# High-Level_PCB_v3_0.net
KiCad netlist of a schematic drawn in EAGLE
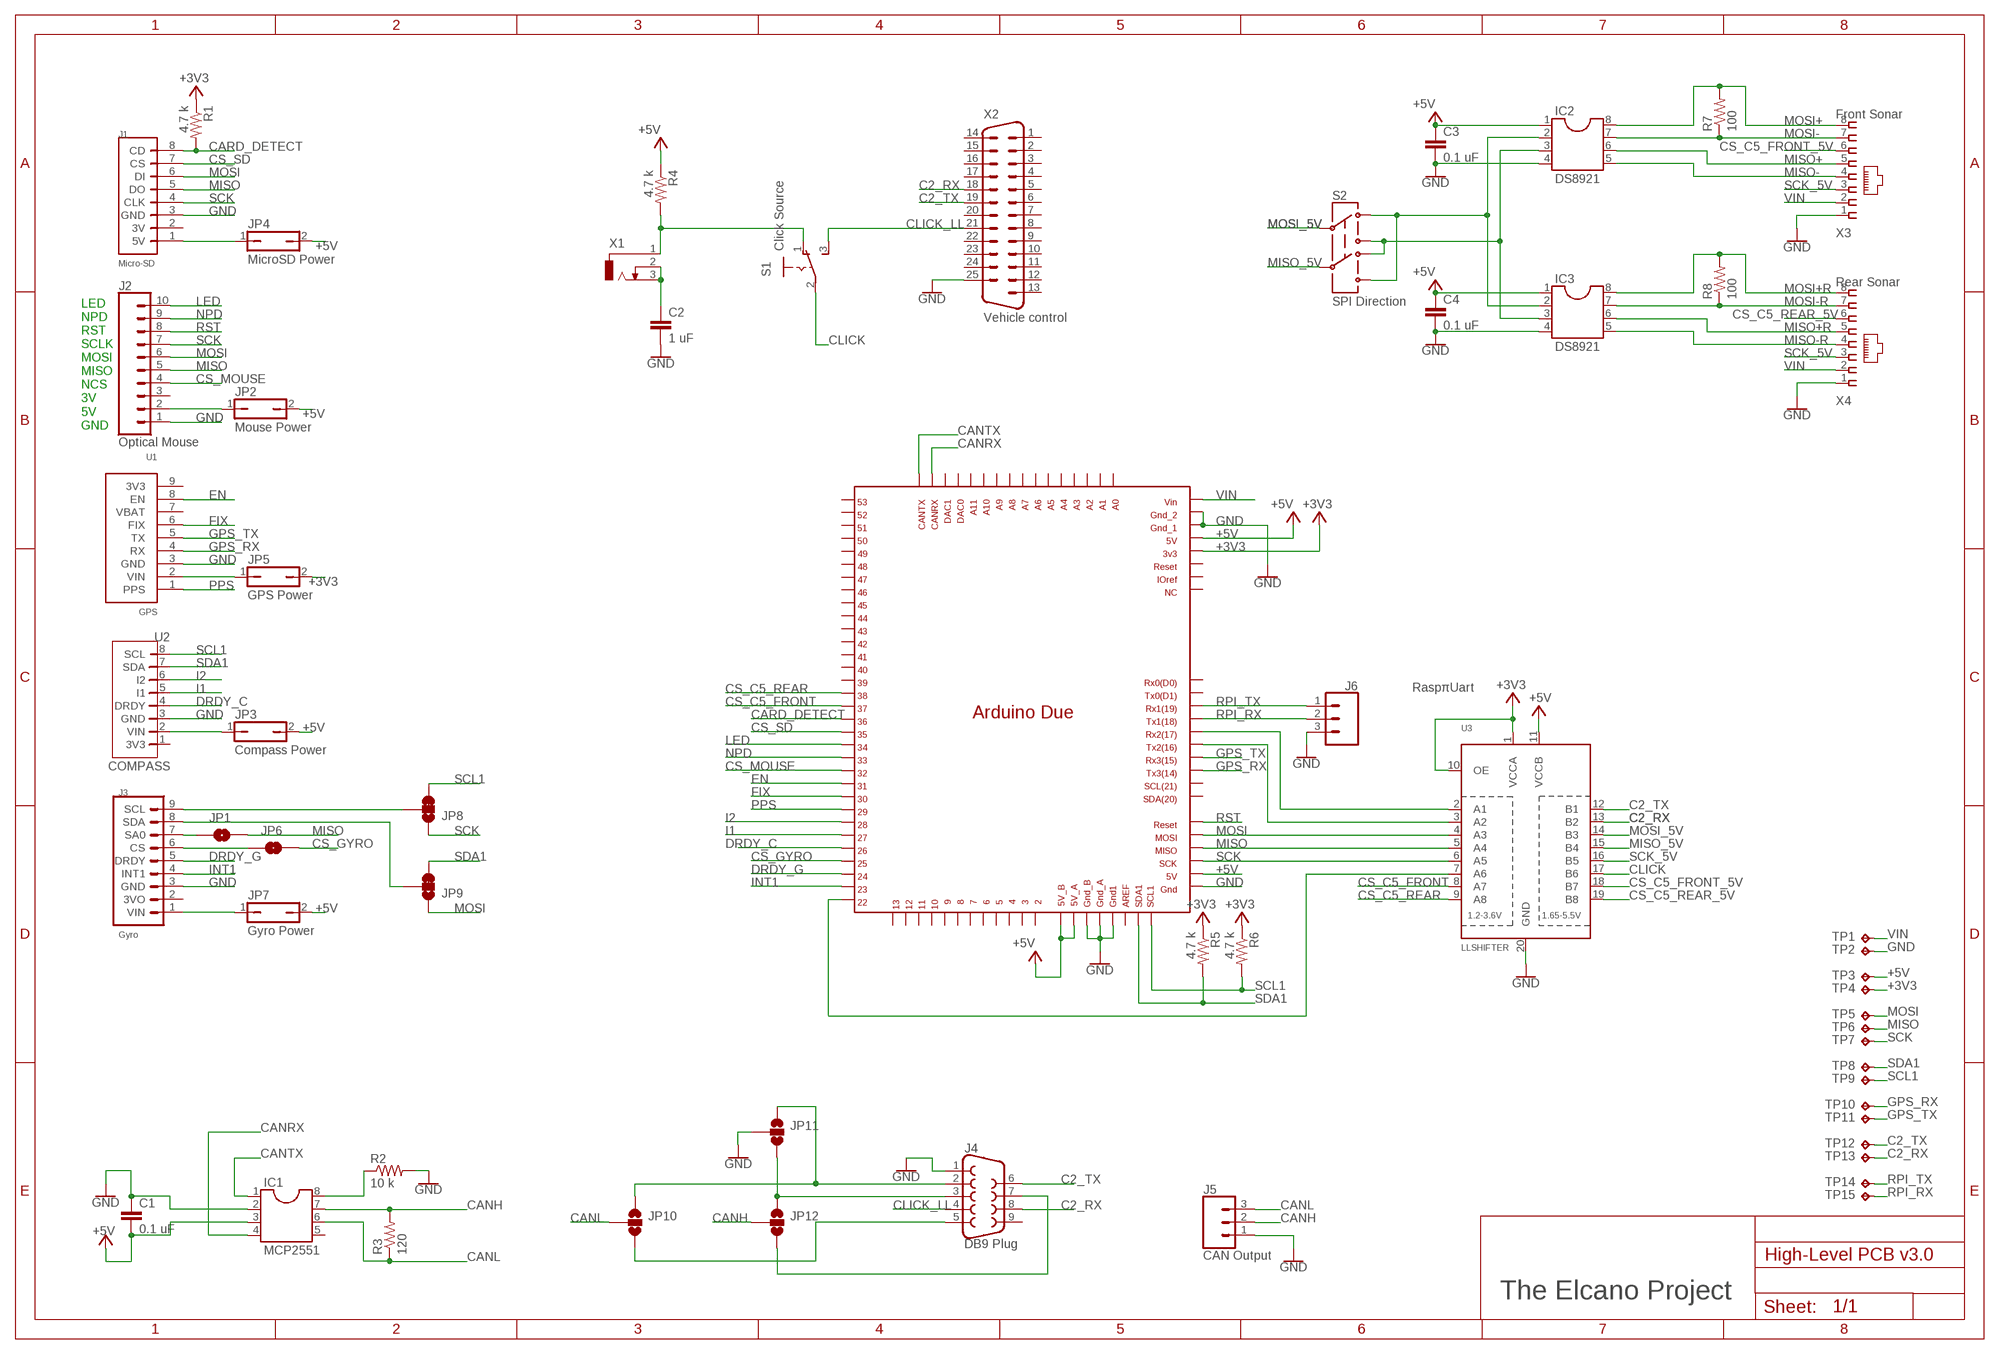
[diagram p0: schematic, sheet 1]

(export (version "E")
  (design (tool "Eeschema 10.0.6"))
  (components
    (comp (ref "C1")
      (value "0.1 uF")
      (footprint "eagle-import:C2.5-5")
      (libsource (lib "eagle-import") (part "C2.5/5"))
    )
    (comp (ref "C2")
      (value "1 uF")
      (footprint "eagle-import:C2.5-5")
      (libsource (lib "eagle-import") (part "C2.5/5"))
    )
    (comp (ref "C3")
      (value "0.1 uF")
      (footprint "eagle-import:C2.5-5")
      (libsource (lib "eagle-import") (part "C2.5/5"))
    )
    (comp (ref "C4")
      (value "0.1 uF")
      (footprint "eagle-import:C2.5-5")
      (libsource (lib "eagle-import") (part "C2.5/5"))
    )
    (comp (ref "IC1")
      (value "MCP2551")
      (footprint "eagle-import:DIL08")
      (libsource (lib "eagle-import") (part "DIL8"))
    )
    (comp (ref "IC2")
      (value "DS8921")
      (footprint "eagle-import:DIL08")
      (libsource (lib "eagle-import") (part "DIL8"))
    )
    (comp (ref "IC3")
      (value "DS8921")
      (footprint "eagle-import:DIL08")
      (libsource (lib "eagle-import") (part "DIL8"))
    )
    (comp (ref "J1")
      (value "Micro-SD")
      (footprint "eagle-import:ELSDCARD")
      (libsource (lib "eagle-import") (part "MINI_SD"))
    )
    (comp (ref "J2")
      (value "Optical Mouse")
      (footprint "eagle-import:1X10")
      (libsource (lib "eagle-import") (part "CONN_10{dblquote}"))
    )
    (comp (ref "J3")
      (value "Gyro")
      (footprint "eagle-import:ELGYRO")
      (libsource (lib "eagle-import") (part "ELGYRO_L3GD20H"))
    )
    (comp (ref "J4")
      (value "DB9 Plug")
      (footprint "eagle-import:DB9_MALE")
      (fields (field (name "SPICEPREFIX") "X"))
      (libsource (lib "eagle-import") (part "DB9MALE"))
    )
    (comp (ref "J5")
      (value "CAN Output")
      (footprint "eagle-import:SCREWTERMINAL-5MM-3")
      (libsource (lib "eagle-import") (part "CONN_03-SCREW-5MM"))
    )
    (comp (ref "J6")
      (value "RaspπUart")
      (footprint "eagle-import:1X03")
      (libsource (lib "eagle-import") (part "TXRX_2RSPPI"))
    )
    (comp (ref "JP1")
      (value "JUMPER-SMT_2_NO_SILK")
      (footprint "eagle-import:SMT-JUMPER_2_NO_SILK")
      (libsource (lib "eagle-import") (part "JUMPER-SMT_2_NO_SILK"))
    )
    (comp (ref "JP2")
      (value "Mouse Power")
      (footprint "eagle-import:JP1")
      (libsource (lib "eagle-import") (part "JP1Q"))
    )
    (comp (ref "JP3")
      (value "Compass Power")
      (footprint "eagle-import:JP1")
      (libsource (lib "eagle-import") (part "JP1Q"))
    )
    (comp (ref "JP4")
      (value "MicroSD Power")
      (footprint "eagle-import:JP1")
      (libsource (lib "eagle-import") (part "JP1Q"))
    )
    (comp (ref "JP5")
      (value "GPS Power")
      (footprint "eagle-import:JP1")
      (libsource (lib "eagle-import") (part "JP1Q"))
    )
    (comp (ref "JP6")
      (value "JUMPER-SMT_2_NO_SILK")
      (footprint "eagle-import:SMT-JUMPER_2_NO_SILK")
      (libsource (lib "eagle-import") (part "JUMPER-SMT_2_NO_SILK"))
    )
    (comp (ref "JP7")
      (value "Gyro Power")
      (footprint "eagle-import:JP1")
      (libsource (lib "eagle-import") (part "JP1Q"))
    )
    (comp (ref "JP8")
      (value "JUMPER-SMT_3_1-NC_TRACE_SILK")
      (footprint "eagle-import:SMT-JUMPER_3_1-NC_TRACE_SILK")
      (libsource (lib "eagle-import") (part "JUMPER-SMT_3_1-NC_TRACE_SILK"))
    )
    (comp (ref "JP9")
      (value "JUMPER-SMT_3_1-NC_TRACE_SILK")
      (footprint "eagle-import:SMT-JUMPER_3_1-NC_TRACE_SILK")
      (libsource (lib "eagle-import") (part "JUMPER-SMT_3_1-NC_TRACE_SILK"))
    )
    (comp (ref "JP10")
      (value "JUMPER-SMT_3_NO_SILK")
      (footprint "eagle-import:SMT-JUMPER_3_NO_SILK")
      (libsource (lib "eagle-import") (part "JUMPER-SMT_3_NO_SILK"))
    )
    (comp (ref "JP11")
      (value "JUMPER-SMT_3_NO_SILK")
      (footprint "eagle-import:SMT-JUMPER_3_NO_SILK")
      (libsource (lib "eagle-import") (part "JUMPER-SMT_3_NO_SILK"))
    )
    (comp (ref "JP12")
      (value "JUMPER-SMT_3_NO_SILK")
      (footprint "eagle-import:SMT-JUMPER_3_NO_SILK")
      (libsource (lib "eagle-import") (part "JUMPER-SMT_3_NO_SILK"))
    )
    (comp (ref "MCU1")
      (value "DUE(NORMAL)")
      (footprint "eagle-import:DUE(NORMAL)")
      (libsource (lib "eagle-import") (part "DUE(NORMAL)"))
    )
    (comp (ref "R1")
      (value "4.7 k")
      (footprint "eagle-import:0204_7")
      (libsource (lib "eagle-import") (part "resistor_348_R-US_0204/7"))
    )
    (comp (ref "R2")
      (value "10 k")
      (footprint "eagle-import:0204_7")
      (libsource (lib "eagle-import") (part "R-US_0204/7"))
    )
    (comp (ref "R3")
      (value "120")
      (footprint "eagle-import:0204_7")
      (libsource (lib "eagle-import") (part "R-US_0204/7"))
    )
    (comp (ref "R4")
      (value "4.7 k")
      (footprint "eagle-import:0204_7")
      (libsource (lib "eagle-import") (part "resistor_348_R-US_0204/7"))
    )
    (comp (ref "R5")
      (value "4.7 k")
      (footprint "eagle-import:0204_7")
      (libsource (lib "eagle-import") (part "resistor_348_R-US_0204/7"))
    )
    (comp (ref "R6")
      (value "4.7 k")
      (footprint "eagle-import:0204_7")
      (libsource (lib "eagle-import") (part "resistor_348_R-US_0204/7"))
    )
    (comp (ref "R7")
      (value "100")
      (footprint "eagle-import:0204_7")
      (libsource (lib "eagle-import") (part "R-US_0204/7"))
    )
    (comp (ref "R8")
      (value "100")
      (footprint "eagle-import:0204_7")
      (libsource (lib "eagle-import") (part "R-US_0204/7"))
    )
    (comp (ref "S1")
      (value "Click Source")
      (footprint "eagle-import:255SB")
      (libsource (lib "eagle-import") (part "255SB"))
    )
    (comp (ref "S2")
      (value "SPI Direction")
      (footprint "eagle-import:DPDT")
      (libsource (lib "eagle-import") (part "DPDT"))
    )
    (comp (ref "TP1")
      (value "TPPAD1-17")
      (footprint "eagle-import:P1-17")
      (libsource (lib "eagle-import") (part "TPPAD1-17"))
    )
    (comp (ref "TP2")
      (value "TPPAD1-17")
      (footprint "eagle-import:P1-17")
      (libsource (lib "eagle-import") (part "TPPAD1-17"))
    )
    (comp (ref "TP3")
      (value "TPPAD1-17")
      (footprint "eagle-import:P1-17")
      (libsource (lib "eagle-import") (part "TPPAD1-17"))
    )
    (comp (ref "TP4")
      (value "TPPAD1-17")
      (footprint "eagle-import:P1-17")
      (libsource (lib "eagle-import") (part "TPPAD1-17"))
    )
    (comp (ref "TP5")
      (value "TPPAD1-17")
      (footprint "eagle-import:P1-17")
      (libsource (lib "eagle-import") (part "TPPAD1-17"))
    )
    (comp (ref "TP6")
      (value "TPPAD1-17")
      (footprint "eagle-import:P1-17")
      (libsource (lib "eagle-import") (part "TPPAD1-17"))
    )
    (comp (ref "TP7")
      (value "TPPAD1-17")
      (footprint "eagle-import:P1-17")
      (libsource (lib "eagle-import") (part "TPPAD1-17"))
    )
    (comp (ref "TP8")
      (value "TPPAD1-17")
      (footprint "eagle-import:P1-17")
      (libsource (lib "eagle-import") (part "TPPAD1-17"))
    )
    (comp (ref "TP9")
      (value "TPPAD1-17")
      (footprint "eagle-import:P1-17")
      (libsource (lib "eagle-import") (part "TPPAD1-17"))
    )
    (comp (ref "TP10")
      (value "TPPAD1-17")
      (footprint "eagle-import:P1-17")
      (libsource (lib "eagle-import") (part "TPPAD1-17"))
    )
    (comp (ref "TP11")
      (value "TPPAD1-17")
      (footprint "eagle-import:P1-17")
      (libsource (lib "eagle-import") (part "TPPAD1-17"))
    )
    (comp (ref "TP12")
      (value "TPPAD1-17")
      (footprint "eagle-import:P1-17")
      (libsource (lib "eagle-import") (part "TPPAD1-17"))
    )
    (comp (ref "TP13")
      (value "TPPAD1-17")
      (footprint "eagle-import:P1-17")
      (libsource (lib "eagle-import") (part "TPPAD1-17"))
    )
    (comp (ref "TP14")
      (value "TPPAD1-17")
      (footprint "eagle-import:P1-17")
      (libsource (lib "eagle-import") (part "TPPAD1-17"))
    )
    (comp (ref "TP15")
      (value "TPPAD1-17")
      (footprint "eagle-import:P1-17")
      (libsource (lib "eagle-import") (part "TPPAD1-17"))
    )
    (comp (ref "U1")
      (value "GPS")
      (footprint "eagle-import:ELGPS")
      (libsource (lib "eagle-import") (part "ELGPS"))
    )
    (comp (ref "U2")
      (value "COMPASS")
      (footprint "eagle-import:ELCOMPASS")
      (libsource (lib "eagle-import") (part "ELCOMPASS"))
    )
    (comp (ref "U3")
      (value "LLSHIFTER")
      (footprint "eagle-import:ELSHIFTER")
      (libsource (lib "eagle-import") (part "ELSHIFTER"))
    )
    (comp (ref "X1")
      (value "2.5MMJACK")
      (footprint "eagle-import:2.5MMJACK")
      (libsource (lib "eagle-import") (part "2.5MMJACK"))
    )
    (comp (ref "X2")
      (value "Vehicle control")
      (footprint "eagle-import:M25H")
      (libsource (lib "eagle-import") (part "M25H"))
    )
    (comp (ref "X3")
      (value "Front Sonar")
      (footprint "eagle-import:RJ45-NO-SHIELD")
      (fields (field (name "MF") "TYCO ELECTRONICS") (field (name "MPN") "RJ45-8L-B"))
      (libsource (lib "eagle-import") (part "RJ45-8L-B"))
    )
    (comp (ref "X4")
      (value "Rear Sonar")
      (footprint "eagle-import:RJ45-NO-SHIELD")
      (fields (field (name "MF") "TYCO ELECTRONICS") (field (name "MPN") "RJ45-8L-B"))
      (libsource (lib "eagle-import") (part "RJ45-8L-B"))
    )
  )
  (nets
    (net (code "1") (name "+3V3") (class "Default")
      (node (ref "JP5") (pin "2") (pinfunction "2_2") (pintype "passive"))
      (node (ref "MCU1") (pin "3V3") (pinfunction "3V3_3V3") (pintype "bidirectional"))
      (node (ref "R1") (pin "1") (pinfunction "1_1") (pintype "passive"))
      (node (ref "R5") (pin "1") (pinfunction "1_1") (pintype "passive"))
      (node (ref "R6") (pin "1") (pinfunction "1_1") (pintype "passive"))
      (node (ref "TP4") (pin "TP") (pinfunction "TP_TP") (pintype "input"))
      (node (ref "U3") (pin "1") (pinfunction "VCCA_1") (pintype "power_in"))
      (node (ref "U3") (pin "10") (pinfunction "OE_10") (pintype "bidirectional"))
    )
    (net (code "2") (name "+5V") (class "Default")
      (node (ref "C1") (pin "2") (pinfunction "2_2") (pintype "passive"))
      (node (ref "C3") (pin "1") (pinfunction "1_1") (pintype "passive"))
      (node (ref "C4") (pin "1") (pinfunction "1_1") (pintype "passive"))
      (node (ref "IC1") (pin "3") (pinfunction "3_3") (pintype "passive"))
      (node (ref "IC2") (pin "1") (pinfunction "1_1") (pintype "passive"))
      (node (ref "IC3") (pin "1") (pinfunction "1_1") (pintype "passive"))
      (node (ref "JP2") (pin "2") (pinfunction "2_2") (pintype "passive"))
      (node (ref "JP3") (pin "2") (pinfunction "2_2") (pintype "passive"))
      (node (ref "JP4") (pin "2") (pinfunction "2_2") (pintype "passive"))
      (node (ref "JP7") (pin "2") (pinfunction "2_2") (pintype "passive"))
      (node (ref "MCU1") (pin "5V") (pinfunction "5V_5V") (pintype "bidirectional"))
      (node (ref "MCU1") (pin "5V_A") (pinfunction "5V_A_5V_A") (pintype "bidirectional"))
      (node (ref "MCU1") (pin "5V_B") (pinfunction "5V_B_5V_B") (pintype "bidirectional"))
      (node (ref "MCU1") (pin "GND_ICSP") (pinfunction "GND_ICSP_GND_ICSP") (pintype "bidirectional"))
      (node (ref "R4") (pin "1") (pinfunction "1_1") (pintype "passive"))
      (node (ref "TP3") (pin "TP") (pinfunction "TP_TP") (pintype "input"))
      (node (ref "U3") (pin "11") (pinfunction "VCCB_11") (pintype "power_in"))
    )
    (net (code "3") (name "/C2_RX") (class "Default")
      (node (ref "J4") (pin "8") (pinfunction "8_8") (pintype "passive"))
      (node (ref "TP13") (pin "TP") (pinfunction "TP_TP") (pintype "input"))
      (node (ref "U3") (pin "13") (pinfunction "B2_13") (pintype "bidirectional"))
      (node (ref "X2") (pin "18") (pinfunction "18_18") (pintype "passive"))
    )
    (net (code "4") (name "/C2_TX") (class "Default")
      (node (ref "J4") (pin "6") (pinfunction "6_6") (pintype "passive"))
      (node (ref "TP12") (pin "TP") (pinfunction "TP_TP") (pintype "input"))
      (node (ref "U3") (pin "12") (pinfunction "B1_12") (pintype "bidirectional"))
      (node (ref "X2") (pin "19") (pinfunction "19_19") (pintype "passive"))
    )
    (net (code "5") (name "/CANH") (class "Default")
      (node (ref "IC1") (pin "7") (pinfunction "7_7") (pintype "passive"))
      (node (ref "J5") (pin "2") (pinfunction "2_2") (pintype "passive"))
      (node (ref "JP12") (pin "2") (pinfunction "2_2") (pintype "passive"))
      (node (ref "R3") (pin "2") (pinfunction "2_2") (pintype "passive"))
    )
    (net (code "6") (name "/CANL") (class "Default")
      (node (ref "IC1") (pin "6") (pinfunction "6_6") (pintype "passive"))
      (node (ref "J5") (pin "3") (pinfunction "3_3") (pintype "passive"))
      (node (ref "JP10") (pin "2") (pinfunction "2_2") (pintype "passive"))
      (node (ref "R3") (pin "1") (pinfunction "1_1") (pintype "passive"))
    )
    (net (code "7") (name "/CANRX") (class "Default")
      (node (ref "IC1") (pin "4") (pinfunction "4_4") (pintype "passive"))
      (node (ref "MCU1") (pin "CANRX") (pinfunction "CANRX_CANRX") (pintype "bidirectional"))
    )
    (net (code "8") (name "/CANTX") (class "Default")
      (node (ref "IC1") (pin "1") (pinfunction "1_1") (pintype "passive"))
      (node (ref "MCU1") (pin "CANTX") (pinfunction "CANTX_CANTX") (pintype "bidirectional"))
    )
    (net (code "9") (name "/CARD_DETECT") (class "Default")
      (node (ref "J1") (pin "8") (pinfunction "CD_8") (pintype "bidirectional"))
      (node (ref "MCU1") (pin "36") (pinfunction "36_36") (pintype "bidirectional"))
      (node (ref "R1") (pin "2") (pinfunction "2_2") (pintype "passive"))
    )
    (net (code "10") (name "/CLICK") (class "Default")
      (node (ref "S1") (pin "2") (pinfunction "P_2") (pintype "passive"))
      (node (ref "U3") (pin "17") (pinfunction "B6_17") (pintype "bidirectional"))
    )
    (net (code "11") (name "/CLICK_LL") (class "Default")
      (node (ref "J4") (pin "4") (pinfunction "4_4") (pintype "passive"))
      (node (ref "S1") (pin "3") (pinfunction "S_3") (pintype "passive"))
      (node (ref "X2") (pin "21") (pinfunction "21_21") (pintype "passive"))
    )
    (net (code "12") (name "/CS_C5_FRONT") (class "Default")
      (node (ref "MCU1") (pin "37") (pinfunction "37_37") (pintype "bidirectional"))
      (node (ref "U3") (pin "8") (pinfunction "A7_8") (pintype "bidirectional"))
    )
    (net (code "13") (name "/CS_C5_FRONT_5V") (class "Default")
      (node (ref "U3") (pin "18") (pinfunction "B7_18") (pintype "bidirectional"))
      (node (ref "X3") (pin "6") (pinfunction "6_6") (pintype "passive"))
    )
    (net (code "14") (name "/CS_C5_REAR") (class "Default")
      (node (ref "MCU1") (pin "38") (pinfunction "38_38") (pintype "bidirectional"))
      (node (ref "U3") (pin "9") (pinfunction "A8_9") (pintype "bidirectional"))
    )
    (net (code "15") (name "/CS_C5_REAR_5V") (class "Default")
      (node (ref "U3") (pin "19") (pinfunction "B8_19") (pintype "bidirectional"))
      (node (ref "X4") (pin "6") (pinfunction "6_6") (pintype "passive"))
    )
    (net (code "16") (name "/CS_GYRO") (class "Default")
      (node (ref "JP6") (pin "2") (pinfunction "2_2") (pintype "passive"))
      (node (ref "MCU1") (pin "25") (pinfunction "25_25") (pintype "bidirectional"))
    )
    (net (code "17") (name "/CS_MOUSE") (class "Default")
      (node (ref "J2") (pin "4") (pinfunction "4_4") (pintype "passive"))
      (node (ref "MCU1") (pin "32") (pinfunction "32_32") (pintype "bidirectional"))
    )
    (net (code "18") (name "/CS_SD") (class "Default")
      (node (ref "J1") (pin "7") (pinfunction "CS_7") (pintype "bidirectional"))
      (node (ref "MCU1") (pin "35") (pinfunction "35_35") (pintype "bidirectional"))
    )
    (net (code "19") (name "/DRDY_C") (class "Default")
      (node (ref "MCU1") (pin "26") (pinfunction "26_26") (pintype "bidirectional"))
      (node (ref "U2") (pin "4") (pinfunction "DRDY_4") (pintype "bidirectional"))
    )
    (net (code "20") (name "/DRDY_G") (class "Default")
      (node (ref "J3") (pin "5") (pinfunction "DRDY_5") (pintype "passive"))
      (node (ref "MCU1") (pin "24") (pinfunction "24_24") (pintype "bidirectional"))
    )
    (net (code "21") (name "/EN") (class "Default")
      (node (ref "MCU1") (pin "31") (pinfunction "31_31") (pintype "bidirectional"))
      (node (ref "U1") (pin "8") (pinfunction "EN_8") (pintype "bidirectional"))
    )
    (net (code "22") (name "/FIX") (class "Default")
      (node (ref "MCU1") (pin "30") (pinfunction "30_30") (pintype "bidirectional"))
      (node (ref "U1") (pin "6") (pinfunction "FIX_6") (pintype "bidirectional"))
    )
    (net (code "23") (name "/GPS_RX") (class "Default")
      (node (ref "MCU1") (pin "TX3") (pinfunction "TX3_TX3") (pintype "bidirectional"))
      (node (ref "TP10") (pin "TP") (pinfunction "TP_TP") (pintype "input"))
      (node (ref "U1") (pin "4") (pinfunction "RX_4") (pintype "input"))
    )
    (net (code "24") (name "/GPS_TX") (class "Default")
      (node (ref "MCU1") (pin "RX3") (pinfunction "RX3_RX3") (pintype "bidirectional"))
      (node (ref "TP11") (pin "TP") (pinfunction "TP_TP") (pintype "input"))
      (node (ref "U1") (pin "5") (pinfunction "TX_5") (pintype "output"))
    )
    (net (code "25") (name "/I1") (class "Default")
      (node (ref "MCU1") (pin "27") (pinfunction "27_27") (pintype "bidirectional"))
      (node (ref "U2") (pin "5") (pinfunction "I1_5") (pintype "bidirectional"))
    )
    (net (code "26") (name "/I2") (class "Default")
      (node (ref "MCU1") (pin "28") (pinfunction "28_28") (pintype "bidirectional"))
      (node (ref "U2") (pin "6") (pinfunction "I2_6") (pintype "bidirectional"))
    )
    (net (code "27") (name "/INT1") (class "Default")
      (node (ref "J3") (pin "4") (pinfunction "INT1_4") (pintype "passive"))
      (node (ref "MCU1") (pin "23") (pinfunction "23_23") (pintype "bidirectional"))
    )
    (net (code "28") (name "/LED") (class "Default")
      (node (ref "J2") (pin "10") (pinfunction "10_10") (pintype "passive"))
      (node (ref "MCU1") (pin "34") (pinfunction "34_34") (pintype "bidirectional"))
    )
    (net (code "29") (name "/MISO") (class "Default")
      (node (ref "J1") (pin "5") (pinfunction "DO_5") (pintype "bidirectional"))
      (node (ref "J2") (pin "5") (pinfunction "5_5") (pintype "passive"))
      (node (ref "JP1") (pin "2") (pinfunction "2_2") (pintype "passive"))
      (node (ref "MCU1") (pin "MISO_ICSP") (pinfunction "MISO_ICSP_MISO_ICSP") (pintype "bidirectional"))
      (node (ref "TP6") (pin "TP") (pinfunction "TP_TP") (pintype "input"))
      (node (ref "U3") (pin "5") (pinfunction "A4_5") (pintype "bidirectional"))
    )
    (net (code "30") (name "/MISO+") (class "Default")
      (node (ref "IC2") (pin "6") (pinfunction "6_6") (pintype "passive"))
      (node (ref "X3") (pin "5") (pinfunction "5_5") (pintype "passive"))
    )
    (net (code "31") (name "/MISO+R") (class "Default")
      (node (ref "IC3") (pin "6") (pinfunction "6_6") (pintype "passive"))
      (node (ref "X4") (pin "5") (pinfunction "5_5") (pintype "passive"))
    )
    (net (code "32") (name "/MISO-") (class "Default")
      (node (ref "IC2") (pin "5") (pinfunction "5_5") (pintype "passive"))
      (node (ref "X3") (pin "4") (pinfunction "4_4") (pintype "passive"))
    )
    (net (code "33") (name "/MISO-R") (class "Default")
      (node (ref "IC3") (pin "5") (pinfunction "5_5") (pintype "passive"))
      (node (ref "X4") (pin "4") (pinfunction "4_4") (pintype "passive"))
    )
    (net (code "34") (name "/MISO_5V") (class "Default")
      (node (ref "S2") (pin "5") (pinfunction "5_5") (pintype "bidirectional"))
      (node (ref "U3") (pin "15") (pinfunction "B4_15") (pintype "bidirectional"))
    )
    (net (code "35") (name "/MOSI") (class "Default")
      (node (ref "J1") (pin "6") (pinfunction "DI_6") (pintype "bidirectional"))
      (node (ref "J2") (pin "6") (pinfunction "6_6") (pintype "passive"))
      (node (ref "JP9") (pin "1") (pinfunction "1_1") (pintype "passive"))
      (node (ref "MCU1") (pin "MOSI_ICSP") (pinfunction "MOSI_ICSP_MOSI_ICSP") (pintype "bidirectional"))
      (node (ref "TP5") (pin "TP") (pinfunction "TP_TP") (pintype "input"))
      (node (ref "U3") (pin "4") (pinfunction "A3_4") (pintype "bidirectional"))
    )
    (net (code "36") (name "/MOSI+") (class "Default")
      (node (ref "IC2") (pin "8") (pinfunction "8_8") (pintype "passive"))
      (node (ref "R7") (pin "2") (pinfunction "2_2") (pintype "passive"))
      (node (ref "X3") (pin "8") (pinfunction "8_8") (pintype "passive"))
    )
    (net (code "37") (name "/MOSI+R") (class "Default")
      (node (ref "IC3") (pin "8") (pinfunction "8_8") (pintype "passive"))
      (node (ref "R8") (pin "2") (pinfunction "2_2") (pintype "passive"))
      (node (ref "X4") (pin "8") (pinfunction "8_8") (pintype "passive"))
    )
    (net (code "38") (name "/MOSI-") (class "Default")
      (node (ref "IC2") (pin "7") (pinfunction "7_7") (pintype "passive"))
      (node (ref "R7") (pin "1") (pinfunction "1_1") (pintype "passive"))
      (node (ref "X3") (pin "7") (pinfunction "7_7") (pintype "passive"))
    )
    (net (code "39") (name "/MOSI-R") (class "Default")
      (node (ref "IC3") (pin "7") (pinfunction "7_7") (pintype "passive"))
      (node (ref "R8") (pin "1") (pinfunction "1_1") (pintype "passive"))
      (node (ref "X4") (pin "7") (pinfunction "7_7") (pintype "passive"))
    )
    (net (code "40") (name "/MOSI_5V") (class "Default")
      (node (ref "S2") (pin "2") (pinfunction "2_2") (pintype "bidirectional"))
      (node (ref "U3") (pin "14") (pinfunction "B3_14") (pintype "bidirectional"))
    )
    (net (code "41") (name "/NPD") (class "Default")
      (node (ref "J2") (pin "9") (pinfunction "9_9") (pintype "passive"))
      (node (ref "MCU1") (pin "33") (pinfunction "33_33") (pintype "bidirectional"))
    )
    (net (code "42") (name "/PPS") (class "Default")
      (node (ref "MCU1") (pin "29") (pinfunction "29_29") (pintype "bidirectional"))
      (node (ref "U1") (pin "1") (pinfunction "PPS_1") (pintype "bidirectional"))
    )
    (net (code "43") (name "/RPI_RX") (class "Default")
      (node (ref "J6") (pin "2") (pinfunction "1_2") (pintype "passive"))
      (node (ref "MCU1") (pin "TX1") (pinfunction "TX1_TX1") (pintype "bidirectional"))
      (node (ref "TP15") (pin "TP") (pinfunction "TP_TP") (pintype "input"))
    )
    (net (code "44") (name "/RPI_TX") (class "Default")
      (node (ref "J6") (pin "1") (pinfunction "2_1") (pintype "passive"))
      (node (ref "MCU1") (pin "RX1") (pinfunction "RX1_RX1") (pintype "bidirectional"))
      (node (ref "TP14") (pin "TP") (pinfunction "TP_TP") (pintype "input"))
    )
    (net (code "45") (name "/RST") (class "Default")
      (node (ref "J2") (pin "8") (pinfunction "8_8") (pintype "passive"))
      (node (ref "MCU1") (pin "RESET_ICSP") (pinfunction "RESET_ICSP_RESET_ICSP") (pintype "bidirectional"))
    )
    (net (code "46") (name "/SCK") (class "Default")
      (node (ref "J1") (pin "4") (pinfunction "CLK_4") (pintype "bidirectional"))
      (node (ref "J2") (pin "7") (pinfunction "7_7") (pintype "passive"))
      (node (ref "JP8") (pin "1") (pinfunction "1_1") (pintype "passive"))
      (node (ref "MCU1") (pin "SCK_ICSP") (pinfunction "SCK_ICSP_SCK_ICSP") (pintype "bidirectional"))
      (node (ref "TP7") (pin "TP") (pinfunction "TP_TP") (pintype "input"))
      (node (ref "U3") (pin "6") (pinfunction "A5_6") (pintype "bidirectional"))
    )
    (net (code "47") (name "/SCK_5V") (class "Default")
      (node (ref "U3") (pin "16") (pinfunction "B5_16") (pintype "bidirectional"))
      (node (ref "X3") (pin "3") (pinfunction "3_3") (pintype "passive"))
      (node (ref "X4") (pin "3") (pinfunction "3_3") (pintype "passive"))
    )
    (net (code "48") (name "/SCL1") (class "Default")
      (node (ref "JP8") (pin "3") (pinfunction "3_3") (pintype "passive"))
      (node (ref "MCU1") (pin "SCL1") (pinfunction "SCL1_SCL1") (pintype "bidirectional"))
      (node (ref "R6") (pin "2") (pinfunction "2_2") (pintype "passive"))
      (node (ref "TP9") (pin "TP") (pinfunction "TP_TP") (pintype "input"))
      (node (ref "U2") (pin "8") (pinfunction "SCL_8") (pintype "bidirectional"))
    )
    (net (code "49") (name "/SDA1") (class "Default")
      (node (ref "JP9") (pin "3") (pinfunction "3_3") (pintype "passive"))
      (node (ref "MCU1") (pin "SDA1") (pinfunction "SDA1_SDA1") (pintype "bidirectional"))
      (node (ref "R5") (pin "2") (pinfunction "2_2") (pintype "passive"))
      (node (ref "TP8") (pin "TP") (pinfunction "TP_TP") (pintype "input"))
      (node (ref "U2") (pin "7") (pinfunction "SDA_7") (pintype "bidirectional"))
    )
    (net (code "50") (name "/VIN") (class "Default")
      (node (ref "MCU1") (pin "VIN") (pinfunction "VIN_VIN") (pintype "bidirectional"))
      (node (ref "TP1") (pin "TP") (pinfunction "TP_TP") (pintype "input"))
      (node (ref "X3") (pin "2") (pinfunction "2_2") (pintype "passive"))
      (node (ref "X4") (pin "2") (pinfunction "2_2") (pintype "passive"))
    )
    (net (code "51") (name "GND") (class "Default")
      (node (ref "C1") (pin "1") (pinfunction "1_1") (pintype "passive"))
      (node (ref "C2") (pin "2") (pinfunction "2_2") (pintype "passive"))
      (node (ref "C3") (pin "2") (pinfunction "2_2") (pintype "passive"))
      (node (ref "C4") (pin "2") (pinfunction "2_2") (pintype "passive"))
      (node (ref "IC1") (pin "2") (pinfunction "2_2") (pintype "passive"))
      (node (ref "IC2") (pin "4") (pinfunction "4_4") (pintype "passive"))
      (node (ref "IC3") (pin "4") (pinfunction "4_4") (pintype "passive"))
      (node (ref "J1") (pin "3") (pinfunction "GND_3") (pintype "bidirectional"))
      (node (ref "J2") (pin "1") (pinfunction "1_1") (pintype "passive"))
      (node (ref "J3") (pin "3") (pinfunction "GND_3") (pintype "passive"))
      (node (ref "J4") (pin "1") (pinfunction "1_1") (pintype "passive"))
      (node (ref "J5") (pin "1") (pinfunction "1_1") (pintype "passive"))
      (node (ref "J6") (pin "3") (pinfunction "3_3") (pintype "passive"))
      (node (ref "JP11") (pin "2") (pinfunction "2_2") (pintype "passive"))
      (node (ref "MCU1") (pin "5V_ICSP") (pinfunction "5V_ICSP_5V_ICSP") (pintype "bidirectional"))
      (node (ref "MCU1") (pin "GND1") (pinfunction "GND1_GND1") (pintype "bidirectional"))
      (node (ref "MCU1") (pin "GND_1") (pinfunction "GND_1_GND_1") (pintype "bidirectional"))
      (node (ref "MCU1") (pin "GND_2") (pinfunction "GND_2_GND_2") (pintype "bidirectional"))
      (node (ref "MCU1") (pin "GND_A") (pinfunction "GND_A_GND_A") (pintype "bidirectional"))
      (node (ref "MCU1") (pin "GND_B") (pinfunction "GND_B_GND_B") (pintype "bidirectional"))
      (node (ref "R2") (pin "2") (pinfunction "2_2") (pintype "passive"))
      (node (ref "TP2") (pin "TP") (pinfunction "TP_TP") (pintype "input"))
      (node (ref "U1") (pin "3") (pinfunction "GND_3") (pintype "power_in"))
      (node (ref "U2") (pin "3") (pinfunction "GND_3") (pintype "power_in"))
      (node (ref "U3") (pin "20") (pinfunction "GND_20") (pintype "power_in"))
      (node (ref "X2") (pin "25") (pinfunction "25_25") (pintype "passive"))
      (node (ref "X3") (pin "1") (pinfunction "1_1") (pintype "passive"))
      (node (ref "X4") (pin "1") (pinfunction "1_1") (pintype "passive"))
    )
    (net (code "52") (name "Net-(C2-Pad1)") (class "Default")
      (node (ref "C2") (pin "1") (pinfunction "1_1") (pintype "passive"))
      (node (ref "X1") (pin "2") (pinfunction "2_2") (pintype "passive"))
      (node (ref "X1") (pin "3") (pinfunction "3_3") (pintype "passive"))
    )
    (net (code "53") (name "Net-(IC1-Pad8)") (class "Default")
      (node (ref "IC1") (pin "8") (pinfunction "8_8") (pintype "passive"))
      (node (ref "R2") (pin "1") (pinfunction "1_1") (pintype "passive"))
    )
    (net (code "54") (name "Net-(IC2-Pad2)") (class "Default")
      (node (ref "IC2") (pin "2") (pinfunction "2_2") (pintype "passive"))
      (node (ref "IC3") (pin "2") (pinfunction "2_2") (pintype "passive"))
      (node (ref "S2") (pin "1") (pinfunction "1_1") (pintype "bidirectional"))
      (node (ref "S2") (pin "6") (pinfunction "6_6") (pintype "bidirectional"))
    )
    (net (code "55") (name "Net-(IC2-Pad3)") (class "Default")
      (node (ref "IC2") (pin "3") (pinfunction "3_3") (pintype "passive"))
      (node (ref "IC3") (pin "3") (pinfunction "3_3") (pintype "passive"))
      (node (ref "S2") (pin "3") (pinfunction "3_3") (pintype "bidirectional"))
      (node (ref "S2") (pin "4") (pinfunction "4_4") (pintype "bidirectional"))
    )
    (net (code "56") (name "Net-(J1-5V)") (class "Default")
      (node (ref "J1") (pin "1") (pinfunction "5V_1") (pintype "bidirectional"))
      (node (ref "JP4") (pin "1") (pinfunction "1_1") (pintype "passive"))
    )
    (net (code "57") (name "Net-(J2-Pad2)") (class "Default")
      (node (ref "J2") (pin "2") (pinfunction "2_2") (pintype "passive"))
      (node (ref "JP2") (pin "1") (pinfunction "1_1") (pintype "passive"))
    )
    (net (code "58") (name "Net-(J3-CS)") (class "Default")
      (node (ref "J3") (pin "6") (pinfunction "CS_6") (pintype "passive"))
      (node (ref "JP6") (pin "1") (pinfunction "1_1") (pintype "passive"))
    )
    (net (code "59") (name "Net-(J3-SA0)") (class "Default")
      (node (ref "J3") (pin "7") (pinfunction "SA0_7") (pintype "passive"))
      (node (ref "JP1") (pin "1") (pinfunction "1_1") (pintype "passive"))
    )
    (net (code "60") (name "Net-(J3-SCL)") (class "Default")
      (node (ref "J3") (pin "9") (pinfunction "SCL_9") (pintype "passive"))
      (node (ref "JP8") (pin "2") (pinfunction "2_2") (pintype "passive"))
    )
    (net (code "61") (name "Net-(J3-SDA)") (class "Default")
      (node (ref "J3") (pin "8") (pinfunction "SDA_8") (pintype "passive"))
      (node (ref "JP9") (pin "2") (pinfunction "2_2") (pintype "passive"))
    )
    (net (code "62") (name "Net-(J3-VIN)") (class "Default")
      (node (ref "J3") (pin "1") (pinfunction "VIN_1") (pintype "passive"))
      (node (ref "JP7") (pin "1") (pinfunction "1_1") (pintype "passive"))
    )
    (net (code "63") (name "Net-(J4-Pad2)") (class "Default")
      (node (ref "J4") (pin "2") (pinfunction "2_2") (pintype "passive"))
      (node (ref "JP10") (pin "1") (pinfunction "1_1") (pintype "passive"))
      (node (ref "JP11") (pin "1") (pinfunction "1_1") (pintype "passive"))
    )
    (net (code "64") (name "Net-(J4-Pad3)") (class "Default")
      (node (ref "J4") (pin "3") (pinfunction "3_3") (pintype "passive"))
      (node (ref "JP11") (pin "3") (pinfunction "3_3") (pintype "passive"))
      (node (ref "JP12") (pin "1") (pinfunction "1_1") (pintype "passive"))
    )
    (net (code "65") (name "Net-(J4-Pad5)") (class "Default")
      (node (ref "J4") (pin "5") (pinfunction "5_5") (pintype "passive"))
      (node (ref "JP10") (pin "3") (pinfunction "3_3") (pintype "passive"))
    )
    (net (code "66") (name "Net-(J4-Pad7)") (class "Default")
      (node (ref "J4") (pin "7") (pinfunction "7_7") (pintype "passive"))
      (node (ref "JP12") (pin "3") (pinfunction "3_3") (pintype "passive"))
    )
    (net (code "67") (name "Net-(S1-O)") (class "Default")
      (node (ref "R4") (pin "2") (pinfunction "2_2") (pintype "passive"))
      (node (ref "S1") (pin "1") (pinfunction "O_1") (pintype "passive"))
      (node (ref "X1") (pin "1") (pinfunction "1_1") (pintype "passive"))
    )
    (net (code "68") (name "Net-(U1-VIN)") (class "Default")
      (node (ref "JP5") (pin "1") (pinfunction "1_1") (pintype "passive"))
      (node (ref "U1") (pin "2") (pinfunction "VIN_2") (pintype "power_in"))
    )
    (net (code "69") (name "Net-(U2-VIN)") (class "Default")
      (node (ref "JP3") (pin "1") (pinfunction "1_1") (pintype "passive"))
      (node (ref "U2") (pin "2") (pinfunction "VIN_2") (pintype "power_in"))
    )
    (net (code "70") (name "Net-(U3-A1)") (class "Default")
      (node (ref "MCU1") (pin "RX2") (pinfunction "RX2_RX2") (pintype "bidirectional"))
      (node (ref "U3") (pin "2") (pinfunction "A1_2") (pintype "bidirectional"))
    )
    (net (code "71") (name "Net-(U3-A2)") (class "Default")
      (node (ref "MCU1") (pin "TX2") (pinfunction "TX2_TX2") (pintype "bidirectional"))
      (node (ref "U3") (pin "3") (pinfunction "A2_3") (pintype "bidirectional"))
    )
    (net (code "72") (name "Net-(U3-A6)") (class "Default")
      (node (ref "MCU1") (pin "22") (pinfunction "22_22") (pintype "bidirectional"))
      (node (ref "U3") (pin "7") (pinfunction "A6_7") (pintype "bidirectional"))
    )
    (net (code "73") (name "unconnected-(IC1-Pad5)") (class "Default")
      (node (ref "IC1") (pin "5") (pinfunction "5_5") (pintype "passive"))
    )
    (net (code "74") (name "unconnected-(J1-3V-Pad2)") (class "Default")
      (node (ref "J1") (pin "2") (pinfunction "3V_2") (pintype "bidirectional"))
    )
    (net (code "75") (name "unconnected-(J2-Pad3)") (class "Default")
      (node (ref "J2") (pin "3") (pinfunction "3_3") (pintype "passive"))
    )
    (net (code "76") (name "unconnected-(J3-3VO-Pad2)") (class "Default")
      (node (ref "J3") (pin "2") (pinfunction "3VO_2") (pintype "passive"))
    )
    (net (code "77") (name "unconnected-(J4-Pad9)") (class "Default")
      (node (ref "J4") (pin "9") (pinfunction "9_9") (pintype "passive"))
    )
    (net (code "78") (name "unconnected-(MCU1-Pad2)") (class "Default")
      (node (ref "MCU1") (pin "2") (pinfunction "2_2") (pintype "bidirectional"))
    )
    (net (code "79") (name "unconnected-(MCU1-Pad3)") (class "Default")
      (node (ref "MCU1") (pin "3") (pinfunction "3_3") (pintype "bidirectional"))
    )
    (net (code "80") (name "unconnected-(MCU1-Pad4)") (class "Default")
      (node (ref "MCU1") (pin "4") (pinfunction "4_4") (pintype "bidirectional"))
    )
    (net (code "81") (name "unconnected-(MCU1-Pad5)") (class "Default")
      (node (ref "MCU1") (pin "5") (pinfunction "5_5") (pintype "bidirectional"))
    )
    (net (code "82") (name "unconnected-(MCU1-Pad6)") (class "Default")
      (node (ref "MCU1") (pin "6") (pinfunction "6_6") (pintype "bidirectional"))
    )
    (net (code "83") (name "unconnected-(MCU1-Pad7)") (class "Default")
      (node (ref "MCU1") (pin "7") (pinfunction "7_7") (pintype "bidirectional"))
    )
    (net (code "84") (name "unconnected-(MCU1-Pad8)") (class "Default")
      (node (ref "MCU1") (pin "8") (pinfunction "8_8") (pintype "bidirectional"))
    )
    (net (code "85") (name "unconnected-(MCU1-Pad9)") (class "Default")
      (node (ref "MCU1") (pin "9") (pinfunction "9_9") (pintype "bidirectional"))
    )
    (net (code "86") (name "unconnected-(MCU1-Pad10)") (class "Default")
      (node (ref "MCU1") (pin "10") (pinfunction "10_10") (pintype "bidirectional"))
    )
    (net (code "87") (name "unconnected-(MCU1-Pad11)") (class "Default")
      (node (ref "MCU1") (pin "11") (pinfunction "11_11") (pintype "bidirectional"))
    )
    (net (code "88") (name "unconnected-(MCU1-Pad12)") (class "Default")
      (node (ref "MCU1") (pin "12") (pinfunction "12_12") (pintype "bidirectional"))
    )
    (net (code "89") (name "unconnected-(MCU1-Pad13)") (class "Default")
      (node (ref "MCU1") (pin "13") (pinfunction "13_13") (pintype "bidirectional"))
    )
    (net (code "90") (name "unconnected-(MCU1-Pad39)") (class "Default")
      (node (ref "MCU1") (pin "39") (pinfunction "39_39") (pintype "bidirectional"))
    )
    (net (code "91") (name "unconnected-(MCU1-Pad40)") (class "Default")
      (node (ref "MCU1") (pin "40") (pinfunction "40_40") (pintype "bidirectional"))
    )
    (net (code "92") (name "unconnected-(MCU1-Pad41)") (class "Default")
      (node (ref "MCU1") (pin "41") (pinfunction "41_41") (pintype "bidirectional"))
    )
    (net (code "93") (name "unconnected-(MCU1-Pad42)") (class "Default")
      (node (ref "MCU1") (pin "42") (pinfunction "42_42") (pintype "bidirectional"))
    )
    (net (code "94") (name "unconnected-(MCU1-Pad43)") (class "Default")
      (node (ref "MCU1") (pin "43") (pinfunction "43_43") (pintype "bidirectional"))
    )
    (net (code "95") (name "unconnected-(MCU1-Pad44)") (class "Default")
      (node (ref "MCU1") (pin "44") (pinfunction "44_44") (pintype "bidirectional"))
    )
    (net (code "96") (name "unconnected-(MCU1-Pad45)") (class "Default")
      (node (ref "MCU1") (pin "45") (pinfunction "45_45") (pintype "bidirectional"))
    )
    (net (code "97") (name "unconnected-(MCU1-Pad46)") (class "Default")
      (node (ref "MCU1") (pin "46") (pinfunction "46_46") (pintype "bidirectional"))
    )
    (net (code "98") (name "unconnected-(MCU1-Pad47)") (class "Default")
      (node (ref "MCU1") (pin "47") (pinfunction "47_47") (pintype "bidirectional"))
    )
    (net (code "99") (name "unconnected-(MCU1-Pad48)") (class "Default")
      (node (ref "MCU1") (pin "48") (pinfunction "48_48") (pintype "bidirectional"))
    )
    (net (code "100") (name "unconnected-(MCU1-Pad49)") (class "Default")
      (node (ref "MCU1") (pin "49") (pinfunction "49_49") (pintype "bidirectional"))
    )
    (net (code "101") (name "unconnected-(MCU1-Pad50)") (class "Default")
      (node (ref "MCU1") (pin "50") (pinfunction "50_50") (pintype "bidirectional"))
    )
    (net (code "102") (name "unconnected-(MCU1-Pad51)") (class "Default")
      (node (ref "MCU1") (pin "51") (pinfunction "51_51") (pintype "bidirectional"))
    )
    (net (code "103") (name "unconnected-(MCU1-Pad52)") (class "Default")
      (node (ref "MCU1") (pin "52") (pinfunction "52_52") (pintype "bidirectional"))
    )
    (net (code "104") (name "unconnected-(MCU1-Pad53)") (class "Default")
      (node (ref "MCU1") (pin "53") (pinfunction "53_53") (pintype "bidirectional"))
    )
    (net (code "105") (name "unconnected-(MCU1-PadA0)") (class "Default")
      (node (ref "MCU1") (pin "A0") (pinfunction "A0_A0") (pintype "bidirectional"))
    )
    (net (code "106") (name "unconnected-(MCU1-PadA1)") (class "Default")
      (node (ref "MCU1") (pin "A1") (pinfunction "A1_A1") (pintype "bidirectional"))
    )
    (net (code "107") (name "unconnected-(MCU1-PadA2)") (class "Default")
      (node (ref "MCU1") (pin "A2") (pinfunction "A2_A2") (pintype "bidirectional"))
    )
    (net (code "108") (name "unconnected-(MCU1-PadA3)") (class "Default")
      (node (ref "MCU1") (pin "A3") (pinfunction "A3_A3") (pintype "bidirectional"))
    )
    (net (code "109") (name "unconnected-(MCU1-PadA4)") (class "Default")
      (node (ref "MCU1") (pin "A4") (pinfunction "A4_A4") (pintype "bidirectional"))
    )
    (net (code "110") (name "unconnected-(MCU1-PadA5)") (class "Default")
      (node (ref "MCU1") (pin "A5") (pinfunction "A5_A5") (pintype "bidirectional"))
    )
    (net (code "111") (name "unconnected-(MCU1-PadA6)") (class "Default")
      (node (ref "MCU1") (pin "A6") (pinfunction "A6_A6") (pintype "bidirectional"))
    )
    (net (code "112") (name "unconnected-(MCU1-PadA7)") (class "Default")
      (node (ref "MCU1") (pin "A7") (pinfunction "A7_A7") (pintype "bidirectional"))
    )
    (net (code "113") (name "unconnected-(MCU1-PadA8)") (class "Default")
      (node (ref "MCU1") (pin "A8") (pinfunction "A8_A8") (pintype "bidirectional"))
    )
    (net (code "114") (name "unconnected-(MCU1-PadA9)") (class "Default")
      (node (ref "MCU1") (pin "A9") (pinfunction "A9_A9") (pintype "bidirectional"))
    )
    (net (code "115") (name "unconnected-(MCU1-PadA10)") (class "Default")
      (node (ref "MCU1") (pin "A10") (pinfunction "A10_A10") (pintype "bidirectional"))
    )
    (net (code "116") (name "unconnected-(MCU1-PadA11)") (class "Default")
      (node (ref "MCU1") (pin "A11") (pinfunction "A11_A11") (pintype "bidirectional"))
    )
    (net (code "117") (name "unconnected-(MCU1-PadAREF)") (class "Default")
      (node (ref "MCU1") (pin "AREF") (pinfunction "AREF_AREF") (pintype "bidirectional"))
    )
    (net (code "118") (name "unconnected-(MCU1-PadDAC0)") (class "Default")
      (node (ref "MCU1") (pin "DAC0") (pinfunction "DAC0_DAC0") (pintype "bidirectional"))
    )
    (net (code "119") (name "unconnected-(MCU1-PadDAC1)") (class "Default")
      (node (ref "MCU1") (pin "DAC1") (pinfunction "DAC1_DAC1") (pintype "bidirectional"))
    )
    (net (code "120") (name "unconnected-(MCU1-PadIOREF)") (class "Default")
      (node (ref "MCU1") (pin "IOREF") (pinfunction "IOREF_IOREF") (pintype "bidirectional"))
    )
    (net (code "121") (name "unconnected-(MCU1-PadNC)") (class "Default")
      (node (ref "MCU1") (pin "NC") (pinfunction "NC_NC") (pintype "bidirectional"))
    )
    (net (code "122") (name "unconnected-(MCU1-PadRESET)") (class "Default")
      (node (ref "MCU1") (pin "RESET") (pinfunction "RESET_RESET") (pintype "bidirectional"))
    )
    (net (code "123") (name "unconnected-(MCU1-PadRX0)") (class "Default")
      (node (ref "MCU1") (pin "RX0") (pinfunction "RX0_RX0") (pintype "bidirectional"))
    )
    (net (code "124") (name "unconnected-(MCU1-PadSCL)") (class "Default")
      (node (ref "MCU1") (pin "SCL") (pinfunction "SCL_SCL") (pintype "bidirectional"))
    )
    (net (code "125") (name "unconnected-(MCU1-PadSDA)") (class "Default")
      (node (ref "MCU1") (pin "SDA") (pinfunction "SDA_SDA") (pintype "bidirectional"))
    )
    (net (code "126") (name "unconnected-(MCU1-PadTX0)") (class "Default")
      (node (ref "MCU1") (pin "TX0") (pinfunction "TX0_TX0") (pintype "bidirectional"))
    )
    (net (code "127") (name "unconnected-(U1-3V3-Pad9)") (class "Default")
      (node (ref "U1") (pin "9") (pinfunction "3V3_9") (pintype "no_connect"))
    )
    (net (code "128") (name "unconnected-(U1-VBAT-Pad7)") (class "Default")
      (node (ref "U1") (pin "7") (pinfunction "VBAT_7") (pintype "no_connect"))
    )
    (net (code "129") (name "unconnected-(U2-3V3-Pad1)") (class "Default")
      (node (ref "U2") (pin "1") (pinfunction "3V3_1") (pintype "no_connect"))
    )
    (net (code "130") (name "unconnected-(X2-Pad1)") (class "Default")
      (node (ref "X2") (pin "1") (pinfunction "1_1") (pintype "passive"))
    )
    (net (code "131") (name "unconnected-(X2-Pad2)") (class "Default")
      (node (ref "X2") (pin "2") (pinfunction "2_2") (pintype "passive"))
    )
    (net (code "132") (name "unconnected-(X2-Pad3)") (class "Default")
      (node (ref "X2") (pin "3") (pinfunction "3_3") (pintype "passive"))
    )
    (net (code "133") (name "unconnected-(X2-Pad4)") (class "Default")
      (node (ref "X2") (pin "4") (pinfunction "4_4") (pintype "passive"))
    )
    (net (code "134") (name "unconnected-(X2-Pad5)") (class "Default")
      (node (ref "X2") (pin "5") (pinfunction "5_5") (pintype "passive"))
    )
    (net (code "135") (name "unconnected-(X2-Pad6)") (class "Default")
      (node (ref "X2") (pin "6") (pinfunction "6_6") (pintype "passive"))
    )
    (net (code "136") (name "unconnected-(X2-Pad7)") (class "Default")
      (node (ref "X2") (pin "7") (pinfunction "7_7") (pintype "passive"))
    )
    (net (code "137") (name "unconnected-(X2-Pad8)") (class "Default")
      (node (ref "X2") (pin "8") (pinfunction "8_8") (pintype "passive"))
    )
    (net (code "138") (name "unconnected-(X2-Pad9)") (class "Default")
      (node (ref "X2") (pin "9") (pinfunction "9_9") (pintype "passive"))
    )
    (net (code "139") (name "unconnected-(X2-Pad10)") (class "Default")
      (node (ref "X2") (pin "10") (pinfunction "10_10") (pintype "passive"))
    )
    (net (code "140") (name "unconnected-(X2-Pad11)") (class "Default")
      (node (ref "X2") (pin "11") (pinfunction "11_11") (pintype "passive"))
    )
    (net (code "141") (name "unconnected-(X2-Pad12)") (class "Default")
      (node (ref "X2") (pin "12") (pinfunction "12_12") (pintype "passive"))
    )
    (net (code "142") (name "unconnected-(X2-Pad13)") (class "Default")
      (node (ref "X2") (pin "13") (pinfunction "13_13") (pintype "passive"))
    )
    (net (code "143") (name "unconnected-(X2-Pad14)") (class "Default")
      (node (ref "X2") (pin "14") (pinfunction "14_14") (pintype "passive"))
    )
    (net (code "144") (name "unconnected-(X2-Pad15)") (class "Default")
      (node (ref "X2") (pin "15") (pinfunction "15_15") (pintype "passive"))
    )
    (net (code "145") (name "unconnected-(X2-Pad16)") (class "Default")
      (node (ref "X2") (pin "16") (pinfunction "16_16") (pintype "passive"))
    )
    (net (code "146") (name "unconnected-(X2-Pad17)") (class "Default")
      (node (ref "X2") (pin "17") (pinfunction "17_17") (pintype "passive"))
    )
    (net (code "147") (name "unconnected-(X2-Pad20)") (class "Default")
      (node (ref "X2") (pin "20") (pinfunction "20_20") (pintype "passive"))
    )
    (net (code "148") (name "unconnected-(X2-Pad22)") (class "Default")
      (node (ref "X2") (pin "22") (pinfunction "22_22") (pintype "passive"))
    )
    (net (code "149") (name "unconnected-(X2-Pad23)") (class "Default")
      (node (ref "X2") (pin "23") (pinfunction "23_23") (pintype "passive"))
    )
    (net (code "150") (name "unconnected-(X2-Pad24)") (class "Default")
      (node (ref "X2") (pin "24") (pinfunction "24_24") (pintype "passive"))
    )
  )
)
